# 5vldo_FETsw.net
KiCad netlist of a schematic drawn in EAGLE
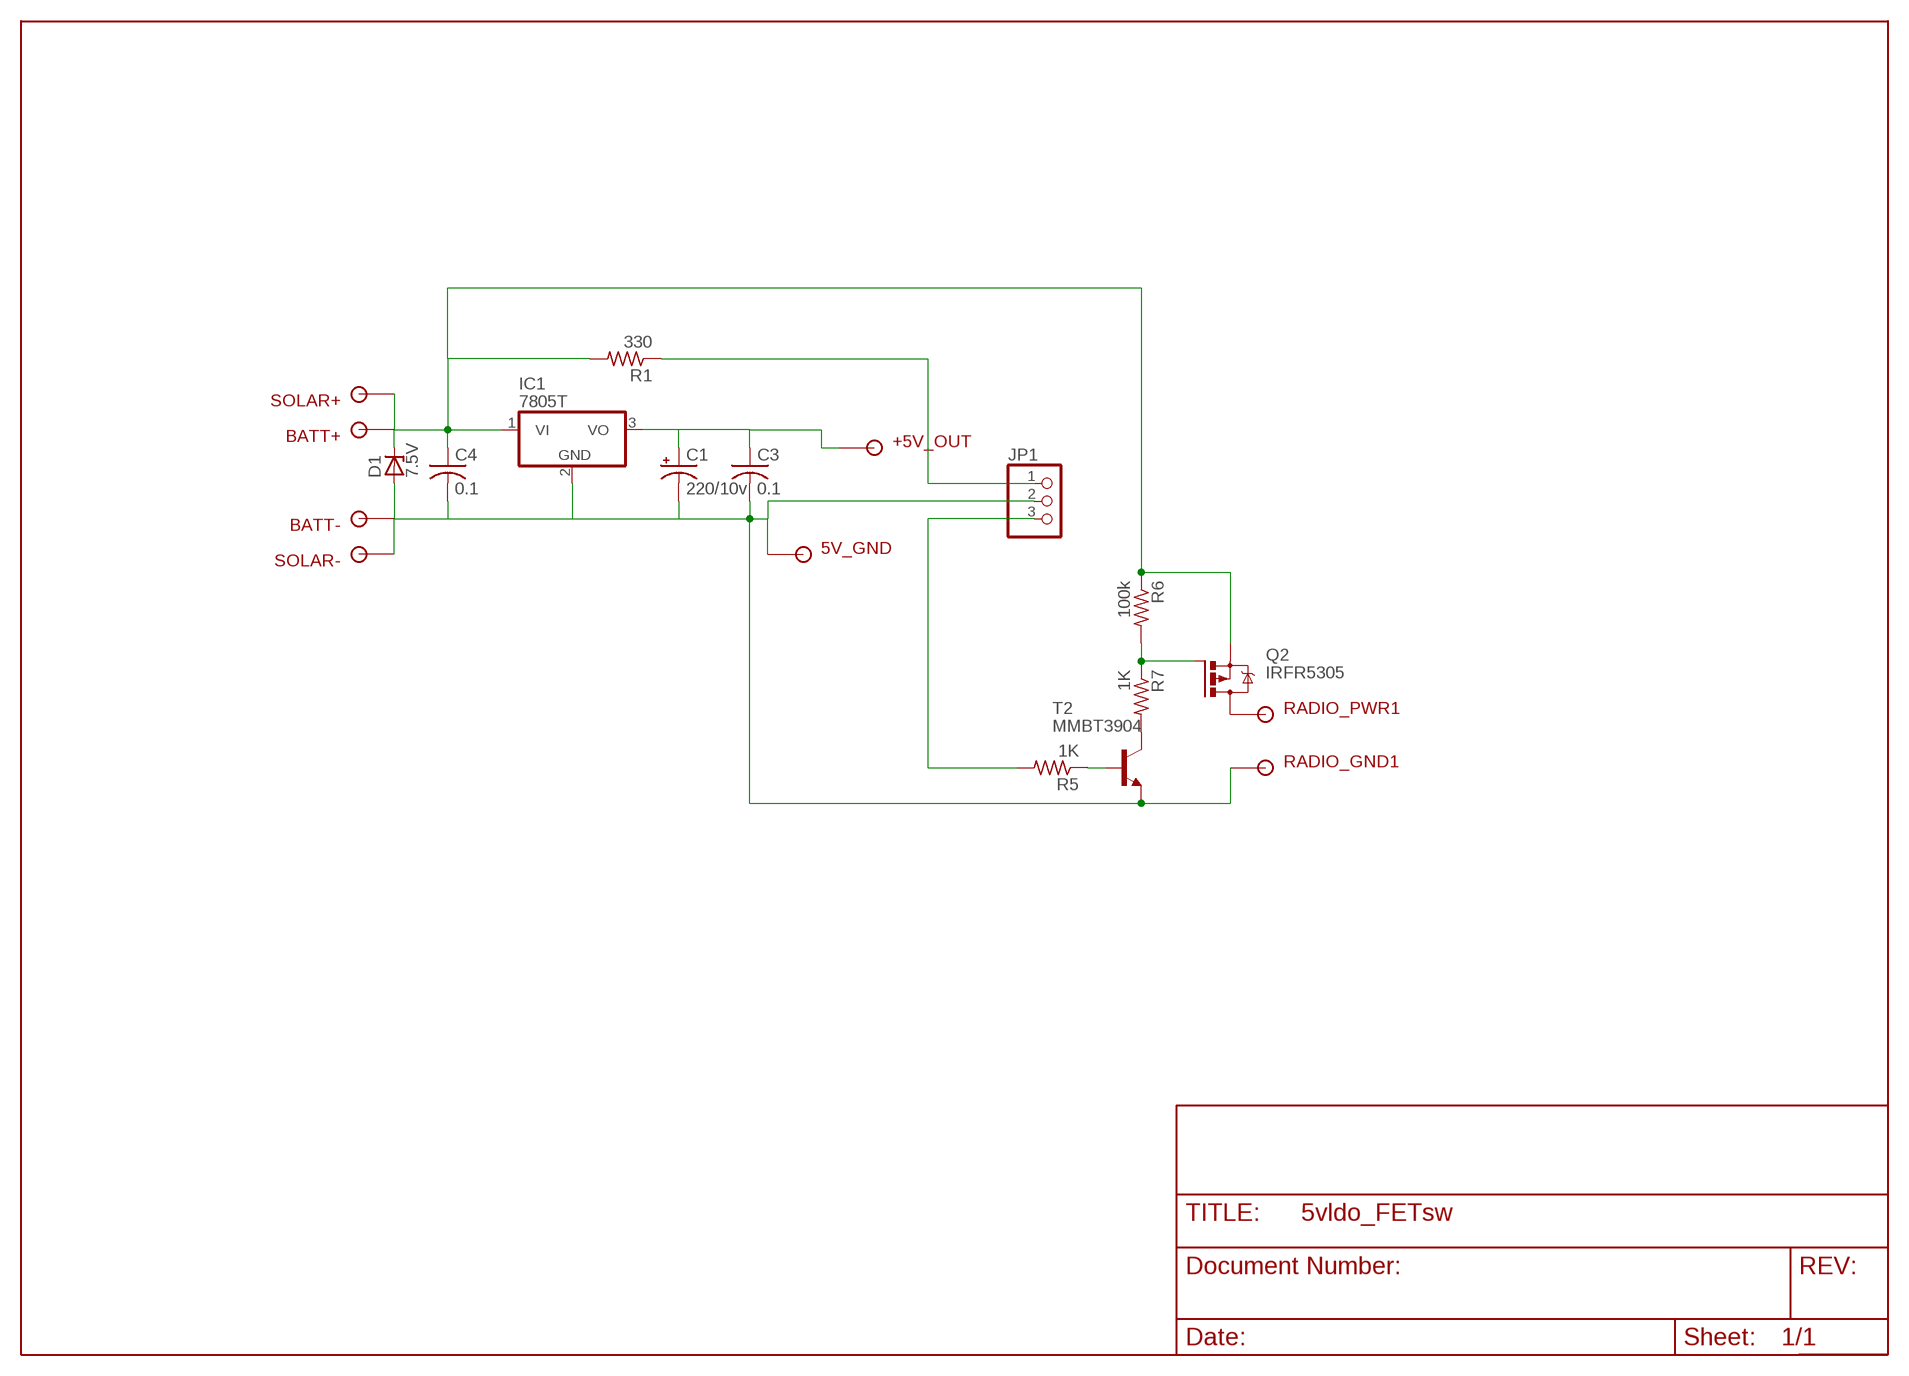
[diagram p0: schematic, sheet 1]

(export (version "E")
  (design (tool "Eeschema 10.0.6"))
  (components
    (comp (ref "+5V_OUT")
      (value "SOLDER_POINTD")
      (footprint "eagle-import:P1-17Y")
      (libsource (lib "eagle-import") (part "SOLDER_POINTD"))
    )
    (comp (ref "5V_GND")
      (value "SOLDER_POINTD")
      (footprint "eagle-import:P1-17Y")
      (libsource (lib "eagle-import") (part "SOLDER_POINTD"))
    )
    (comp (ref "BATT+")
      (value "SOLDER_POINTD")
      (footprint "eagle-import:P1-17Y")
      (libsource (lib "eagle-import") (part "SOLDER_POINTD"))
    )
    (comp (ref "BATT-")
      (value "SOLDER_POINTD")
      (footprint "eagle-import:P1-17Y")
      (libsource (lib "eagle-import") (part "SOLDER_POINTD"))
    )
    (comp (ref "C1")
      (value "220/10v")
      (footprint "eagle-import:SMC_B")
      (libsource (lib "eagle-import") (part "CPOL-USSMCB"))
    )
    (comp (ref "C3")
      (value "0.1")
      (footprint "eagle-import:C0805")
      (libsource (lib "eagle-import") (part "C-USC0805"))
    )
    (comp (ref "C4")
      (value "0.1")
      (footprint "eagle-import:C0805")
      (libsource (lib "eagle-import") (part "C-USC0805"))
    )
    (comp (ref "D1")
      (value "7.5V")
      (footprint "eagle-import:SMB")
      (libsource (lib "eagle-import") (part "ZENER-DIODESMB"))
    )
    (comp (ref "IC1")
      (value "7805T")
      (footprint "eagle-import:TO220H")
      (libsource (lib "eagle-import") (part "78T05"))
    )
    (comp (ref "JP1")
      (value "PINHD-1X3")
      (footprint "eagle-import:1X03")
      (libsource (lib "eagle-import") (part "PINHD-1X3"))
    )
    (comp (ref "Q2")
      (value "IRFR5305")
      (footprint "eagle-import:D-PAK_TO252AA")
      (libsource (lib "eagle-import") (part "IRF?5305R"))
    )
    (comp (ref "R1")
      (value "330")
      (footprint "eagle-import:R0603")
      (libsource (lib "eagle-import") (part "R-US_R0603"))
    )
    (comp (ref "R5")
      (value "1K")
      (footprint "eagle-import:R0603")
      (libsource (lib "eagle-import") (part "R-US_R0603"))
    )
    (comp (ref "R6")
      (value "100k")
      (footprint "eagle-import:R0603")
      (libsource (lib "eagle-import") (part "R-US_R0603"))
    )
    (comp (ref "R7")
      (value "1K")
      (footprint "eagle-import:R0603")
      (libsource (lib "eagle-import") (part "R-US_R0603"))
    )
    (comp (ref "RADIO_GND1")
      (value "SOLDER_POINTD")
      (footprint "eagle-import:P1-17Y")
      (libsource (lib "eagle-import") (part "SOLDER_POINTD"))
    )
    (comp (ref "RADIO_PWR1")
      (value "SOLDER_POINTD")
      (footprint "eagle-import:P1-17Y")
      (libsource (lib "eagle-import") (part "SOLDER_POINTD"))
    )
    (comp (ref "SOLAR+")
      (value "SOLDER_POINTD")
      (footprint "eagle-import:P1-17Y")
      (libsource (lib "eagle-import") (part "SOLDER_POINTD"))
    )
    (comp (ref "SOLAR-")
      (value "SOLDER_POINTD")
      (footprint "eagle-import:P1-17Y")
      (libsource (lib "eagle-import") (part "SOLDER_POINTD"))
    )
    (comp (ref "T2")
      (value "MMBT3904")
      (footprint "eagle-import:SOT23-BEC")
      (libsource (lib "eagle-import") (part "-NPN-SOT23-BECMMBT3904LT1"))
    )
  )
  (nets
    (net (code "1") (name "Net-(+5V_OUT-P$1)") (class "Default")
      (node (ref "+5V_OUT") (pin "1") (pinfunction "P$1_1") (pintype "bidirectional"))
      (node (ref "C1") (pin "+") (pinfunction "+_+") (pintype "passive"))
      (node (ref "C3") (pin "1") (pinfunction "1_1") (pintype "passive"))
      (node (ref "IC1") (pin "3") (pinfunction "VO_3") (pintype "passive"))
    )
    (net (code "2") (name "Net-(5V_GND-P$1)") (class "Default")
      (node (ref "5V_GND") (pin "1") (pinfunction "P$1_1") (pintype "bidirectional"))
      (node (ref "BATT-") (pin "1") (pinfunction "P$1_1") (pintype "bidirectional"))
      (node (ref "C1") (pin "-") (pinfunction "-_-") (pintype "passive"))
      (node (ref "C3") (pin "2") (pinfunction "2_2") (pintype "passive"))
      (node (ref "C4") (pin "2") (pinfunction "2_2") (pintype "passive"))
      (node (ref "D1") (pin "A") (pinfunction "A_A") (pintype "passive"))
      (node (ref "IC1") (pin "2") (pinfunction "GND_2") (pintype "passive"))
      (node (ref "JP1") (pin "2") (pinfunction "2_2") (pintype "passive"))
      (node (ref "RADIO_GND1") (pin "1") (pinfunction "P$1_1") (pintype "bidirectional"))
      (node (ref "SOLAR-") (pin "1") (pinfunction "P$1_1") (pintype "bidirectional"))
      (node (ref "T2") (pin "E") (pinfunction "E_E") (pintype "passive"))
    )
    (net (code "3") (name "Net-(BATT+-P$1)") (class "Default")
      (node (ref "BATT+") (pin "1") (pinfunction "P$1_1") (pintype "bidirectional"))
      (node (ref "C4") (pin "1") (pinfunction "1_1") (pintype "passive"))
      (node (ref "D1") (pin "C") (pinfunction "C_C") (pintype "passive"))
      (node (ref "IC1") (pin "1") (pinfunction "VI_1") (pintype "input"))
      (node (ref "Q2") (pin "3") (pinfunction "S_3") (pintype "passive"))
      (node (ref "R1") (pin "2") (pinfunction "2_2") (pintype "passive"))
      (node (ref "R6") (pin "1") (pinfunction "1_1") (pintype "passive"))
      (node (ref "SOLAR+") (pin "1") (pinfunction "P$1_1") (pintype "bidirectional"))
    )
    (net (code "4") (name "Net-(JP1-Pad1)") (class "Default")
      (node (ref "JP1") (pin "1") (pinfunction "1_1") (pintype "passive"))
      (node (ref "R1") (pin "1") (pinfunction "1_1") (pintype "passive"))
    )
    (net (code "5") (name "Net-(JP1-Pad3)") (class "Default")
      (node (ref "JP1") (pin "3") (pinfunction "3_3") (pintype "passive"))
      (node (ref "R5") (pin "2") (pinfunction "2_2") (pintype "passive"))
    )
    (net (code "6") (name "Net-(Q2-D)") (class "Default")
      (node (ref "Q2") (pin "4") (pinfunction "D_4") (pintype "passive"))
      (node (ref "RADIO_PWR1") (pin "1") (pinfunction "P$1_1") (pintype "bidirectional"))
    )
    (net (code "7") (name "Net-(Q2-G)") (class "Default")
      (node (ref "Q2") (pin "1") (pinfunction "G_1") (pintype "passive"))
      (node (ref "R6") (pin "2") (pinfunction "2_2") (pintype "passive"))
      (node (ref "R7") (pin "1") (pinfunction "1_1") (pintype "passive"))
    )
    (net (code "8") (name "Net-(R5-Pad1)") (class "Default")
      (node (ref "R5") (pin "1") (pinfunction "1_1") (pintype "passive"))
      (node (ref "T2") (pin "B") (pinfunction "B_B") (pintype "passive"))
    )
    (net (code "9") (name "Net-(R7-Pad2)") (class "Default")
      (node (ref "R7") (pin "2") (pinfunction "2_2") (pintype "passive"))
      (node (ref "T2") (pin "C") (pinfunction "C_C") (pintype "passive"))
    )
  )
)
